# POWER.net
KiCad netlist of a schematic drawn in Altium Designer
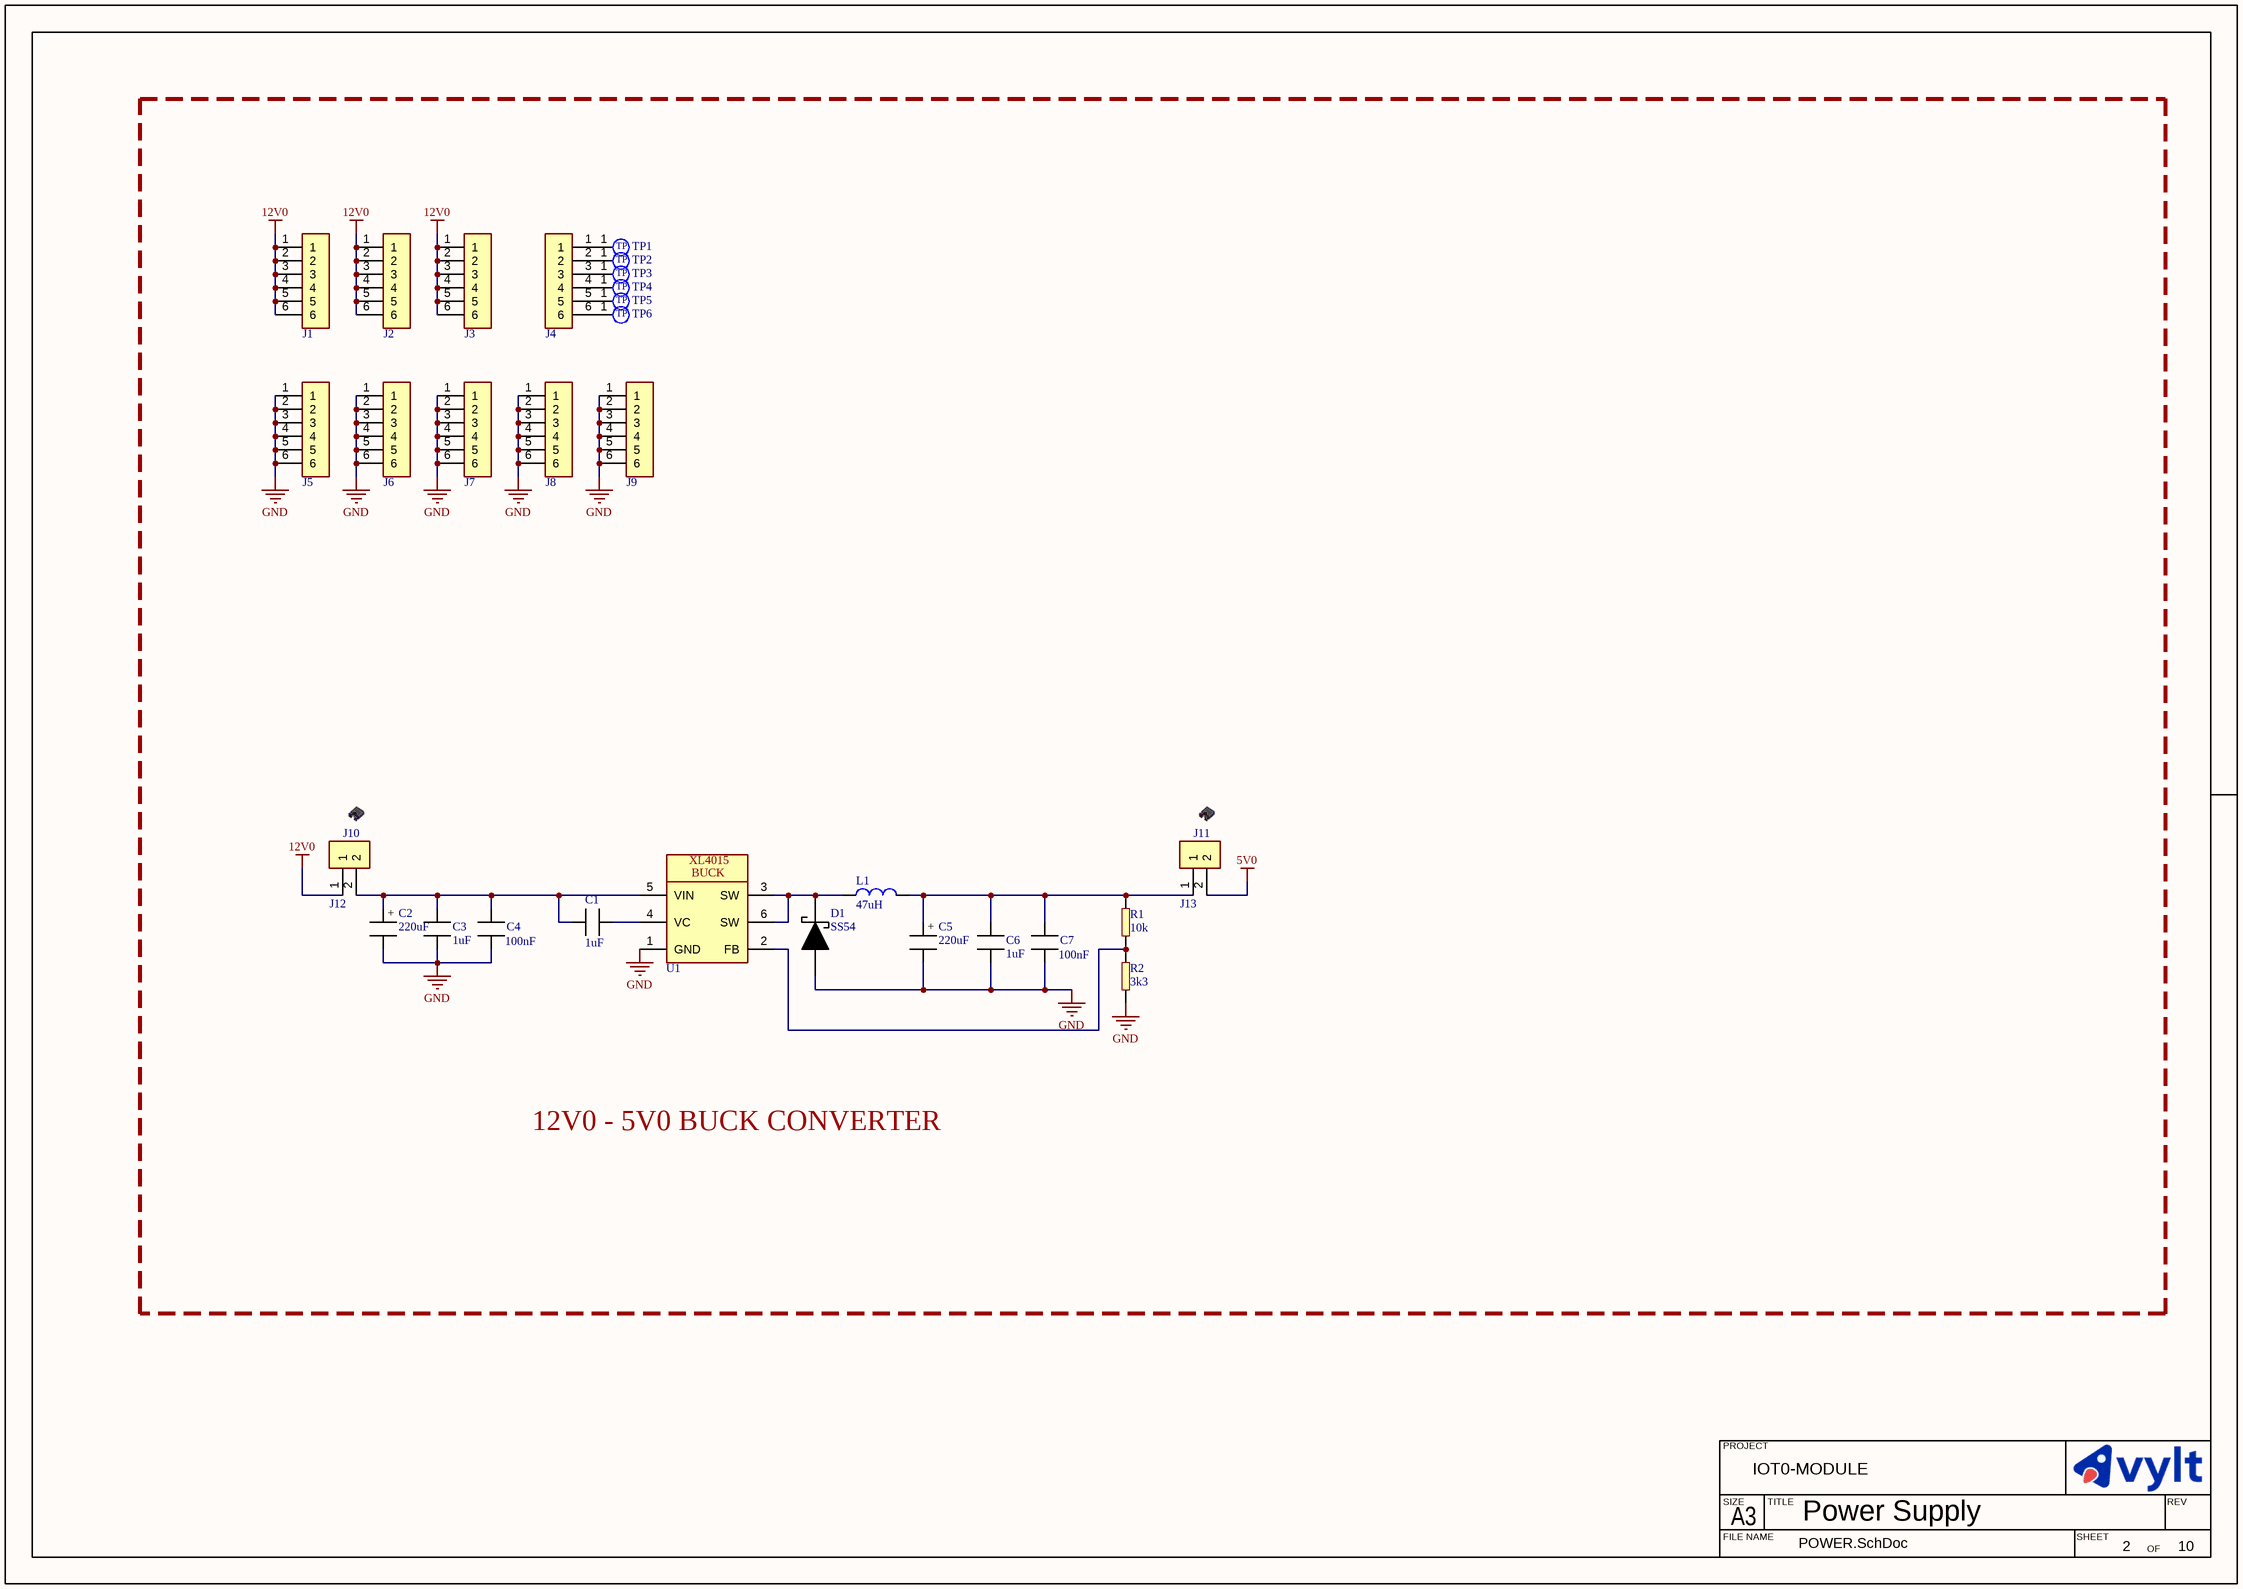
[diagram p0: POWER.SchDoc]

(export (version "E")
  (design (tool "Eeschema 10.0.6"))
  (components
    (comp (ref "C1")
      (value "1uF")
      (footprint "CAPC2012X13L")
      (description "Chip Capacitor, 2-Leads, Body 2.00x1.25mm, IPC High Density")
      (fields (field (name "Comment") "MLCC_0805"))
      (libsource (lib "Capacitor") (part "MLCC_0805"))
    )
    (comp (ref "C2")
      (value "220uF")
      (footprint "CAP_D10_H16_P5 - Flat")
      (description "Electrolytic Capacitor Through Hole D10 P5.0")
      (fields (field (name "Comment") "ERP_102-2"))
      (libsource (lib "ElectrolyticCapacitor") (part "CAP_D10_H16_P5"))
    )
    (comp (ref "C3")
      (value "1uF")
      (footprint "CAPC2012X13L")
      (description "Chip Capacitor, 2-Leads, Body 2.00x1.25mm, IPC High Density")
      (fields (field (name "Comment") "MLCC_0805"))
      (libsource (lib "Capacitor") (part "MLCC_0805"))
    )
    (comp (ref "C4")
      (value "100nF")
      (footprint "CAPC2012X13L")
      (description "Chip Capacitor, 2-Leads, Body 2.00x1.25mm, IPC High Density")
      (fields (field (name "Comment") "MLCC_0805"))
      (libsource (lib "Capacitor") (part "MLCC_0805"))
    )
    (comp (ref "C5")
      (value "220uF")
      (footprint "CAP_D10_H16_P5 - Flat")
      (description "Electrolytic Capacitor Through Hole D10 P5.0")
      (fields (field (name "Comment") "ERP_102-2"))
      (libsource (lib "ElectrolyticCapacitor") (part "CAP_D10_H16_P5"))
    )
    (comp (ref "C6")
      (value "1uF")
      (footprint "CAPC2012X13L")
      (description "Chip Capacitor, 2-Leads, Body 2.00x1.25mm, IPC High Density")
      (fields (field (name "Comment") "MLCC_0805"))
      (libsource (lib "Capacitor") (part "MLCC_0805"))
    )
    (comp (ref "C7")
      (value "100nF")
      (footprint "CAPC2012X13L")
      (description "Chip Capacitor, 2-Leads, Body 2.00x1.25mm, IPC High Density")
      (fields (field (name "Comment") "MLCC_0805"))
      (libsource (lib "Capacitor") (part "MLCC_0805"))
    )
    (comp (ref "D1")
      (value "SS54")
      (footprint "DIOM6959X26L")
      (fields (field (name "Comment") "ERP_104-3"))
      (libsource (lib "Schottky") (part "SS54"))
    )
    (comp (ref "J1")
      (value "6PX1R_M")
      (footprint "6PX1R_M_STK20")
      (description "6PX1R Male Header")
      (libsource (lib "PinHeader") (part "6PX1R_M"))
    )
    (comp (ref "J2")
      (value "6PX1R_M")
      (footprint "6PX1R_M_STK20")
      (description "6PX1R Male Header")
      (libsource (lib "PinHeader") (part "6PX1R_M"))
    )
    (comp (ref "J3")
      (value "6PX1R_M")
      (footprint "6PX1R_M_STK20")
      (description "6PX1R Male Header")
      (libsource (lib "PinHeader") (part "6PX1R_M"))
    )
    (comp (ref "J4")
      (value "6PX1R_M")
      (footprint "6PX1R_M_STK20")
      (description "6PX1R Male Header")
      (libsource (lib "") (part "6PX1R_M_1"))
    )
    (comp (ref "J5")
      (value "6PX1R_M")
      (footprint "6PX1R_M_STK20")
      (description "6PX1R Male Header")
      (libsource (lib "PinHeader") (part "6PX1R_M"))
    )
    (comp (ref "J6")
      (value "6PX1R_M")
      (footprint "6PX1R_M_STK20")
      (description "6PX1R Male Header")
      (libsource (lib "PinHeader") (part "6PX1R_M"))
    )
    (comp (ref "J7")
      (value "6PX1R_M")
      (footprint "6PX1R_M_STK20")
      (description "6PX1R Male Header")
      (libsource (lib "PinHeader") (part "6PX1R_M"))
    )
    (comp (ref "J8")
      (value "6PX1R_M")
      (footprint "6PX1R_M_STK20")
      (description "6PX1R Male Header")
      (libsource (lib "PinHeader") (part "6PX1R_M"))
    )
    (comp (ref "J9")
      (value "6PX1R_M")
      (footprint "6PX1R_M_STK20")
      (description "6PX1R Male Header")
      (libsource (lib "PinHeader") (part "6PX1R_M"))
    )
    (comp (ref "J10")
      (value "Jumper Cap")
      (description "2 Pin Jumper Cap P2.54")
      (libsource (lib "Jumper") (part "Jumper Cap"))
    )
    (comp (ref "J11")
      (value "Jumper Cap")
      (description "2 Pin Jumper Cap P2.54")
      (libsource (lib "Jumper") (part "Jumper Cap"))
    )
    (comp (ref "J12") (value "2PX1R") (footprint "2PX1R") (libsource (lib "PinHeader") (part "2PX1R")))
    (comp (ref "J13") (value "2PX1R") (footprint "2PX1R") (libsource (lib "PinHeader") (part "2PX1R")))
    (comp (ref "L1")
      (value "47uH")
      (footprint "IND_1212")
      (description "IND_1212")
      (fields (field (name "Comment") "ERP_103-3"))
      (libsource (lib "Inductor") (part "IND_1212"))
    )
    (comp (ref "R1")
      (value "10k")
      (footprint "RES_0603")
      (description "RES_0603")
      (fields (field (name "Comment") "ERP_101-1"))
      (libsource (lib "Resistor") (part "RES_0603"))
    )
    (comp (ref "R2")
      (value "3k3")
      (footprint "RES_0603")
      (description "RES_0603")
      (fields (field (name "Comment") "ERP_101-1"))
      (libsource (lib "Resistor") (part "RES_0603"))
    )
    (comp (ref "TP1") (value "TP_1MM") (footprint "TP_1MM") (libsource (lib "Jumper") (part "TP_1MM")))
    (comp (ref "TP2") (value "TP_1MM") (footprint "TP_1MM") (libsource (lib "Jumper") (part "TP_1MM")))
    (comp (ref "TP3") (value "TP_1MM") (footprint "TP_1MM") (libsource (lib "Jumper") (part "TP_1MM")))
    (comp (ref "TP4") (value "TP_1MM") (footprint "TP_1MM") (libsource (lib "Jumper") (part "TP_1MM")))
    (comp (ref "TP5") (value "TP_1MM") (footprint "TP_1MM") (libsource (lib "Jumper") (part "TP_1MM")))
    (comp (ref "TP6") (value "TP_1MM") (footprint "TP_1MM") (libsource (lib "Jumper") (part "TP_1MM")))
    (comp (ref "U1")
      (value "XL4015")
      (footprint "XL4015")
      (description "5A 180KHz 36V Buck DC to DC Converter")
      (libsource (lib "DCDC_Switcher") (part "XL4015"))
    )
  )
  (nets
    (net (code "1") (name "5V0") (class "Default")
      (node (ref "J13") (pin "2") (pinfunction "2_2") (pintype "passive"))
    )
    (net (code "2") (name "12V0") (class "Default")
      (node (ref "J1") (pin "1") (pinfunction "1_1") (pintype "passive"))
      (node (ref "J1") (pin "2") (pinfunction "2_2") (pintype "passive"))
      (node (ref "J1") (pin "3") (pinfunction "3_3") (pintype "passive"))
      (node (ref "J1") (pin "4") (pinfunction "4_4") (pintype "passive"))
      (node (ref "J1") (pin "5") (pinfunction "5_5") (pintype "passive"))
      (node (ref "J1") (pin "6") (pinfunction "6_6") (pintype "passive"))
      (node (ref "J12") (pin "1") (pinfunction "1_1") (pintype "passive"))
      (node (ref "J2") (pin "1") (pinfunction "1_1") (pintype "passive"))
      (node (ref "J2") (pin "2") (pinfunction "2_2") (pintype "passive"))
      (node (ref "J2") (pin "3") (pinfunction "3_3") (pintype "passive"))
      (node (ref "J2") (pin "4") (pinfunction "4_4") (pintype "passive"))
      (node (ref "J2") (pin "5") (pinfunction "5_5") (pintype "passive"))
      (node (ref "J2") (pin "6") (pinfunction "6_6") (pintype "passive"))
      (node (ref "J3") (pin "1") (pinfunction "1_1") (pintype "passive"))
      (node (ref "J3") (pin "2") (pinfunction "2_2") (pintype "passive"))
      (node (ref "J3") (pin "3") (pinfunction "3_3") (pintype "passive"))
      (node (ref "J3") (pin "4") (pinfunction "4_4") (pintype "passive"))
      (node (ref "J3") (pin "5") (pinfunction "5_5") (pintype "passive"))
      (node (ref "J3") (pin "6") (pinfunction "6_6") (pintype "passive"))
    )
    (net (code "3") (name "GND") (class "Default")
      (node (ref "C2") (pin "2") (pinfunction "2_2") (pintype "passive"))
      (node (ref "C3") (pin "1") (pinfunction "1_1") (pintype "passive"))
      (node (ref "C4") (pin "2") (pinfunction "2_2") (pintype "passive"))
      (node (ref "C5") (pin "2") (pinfunction "2_2") (pintype "passive"))
      (node (ref "C6") (pin "1") (pinfunction "1_1") (pintype "passive"))
      (node (ref "C7") (pin "2") (pinfunction "2_2") (pintype "passive"))
      (node (ref "D1") (pin "2") (pinfunction "A_2") (pintype "passive"))
      (node (ref "J5") (pin "1") (pinfunction "1_1") (pintype "passive"))
      (node (ref "J5") (pin "2") (pinfunction "2_2") (pintype "passive"))
      (node (ref "J5") (pin "3") (pinfunction "3_3") (pintype "passive"))
      (node (ref "J5") (pin "4") (pinfunction "4_4") (pintype "passive"))
      (node (ref "J5") (pin "5") (pinfunction "5_5") (pintype "passive"))
      (node (ref "J5") (pin "6") (pinfunction "6_6") (pintype "passive"))
      (node (ref "J6") (pin "1") (pinfunction "1_1") (pintype "passive"))
      (node (ref "J6") (pin "2") (pinfunction "2_2") (pintype "passive"))
      (node (ref "J6") (pin "3") (pinfunction "3_3") (pintype "passive"))
      (node (ref "J6") (pin "4") (pinfunction "4_4") (pintype "passive"))
      (node (ref "J6") (pin "5") (pinfunction "5_5") (pintype "passive"))
      (node (ref "J6") (pin "6") (pinfunction "6_6") (pintype "passive"))
      (node (ref "J7") (pin "1") (pinfunction "1_1") (pintype "passive"))
      (node (ref "J7") (pin "2") (pinfunction "2_2") (pintype "passive"))
      (node (ref "J7") (pin "3") (pinfunction "3_3") (pintype "passive"))
      (node (ref "J7") (pin "4") (pinfunction "4_4") (pintype "passive"))
      (node (ref "J7") (pin "5") (pinfunction "5_5") (pintype "passive"))
      (node (ref "J7") (pin "6") (pinfunction "6_6") (pintype "passive"))
      (node (ref "J8") (pin "1") (pinfunction "1_1") (pintype "passive"))
      (node (ref "J8") (pin "2") (pinfunction "2_2") (pintype "passive"))
      (node (ref "J8") (pin "3") (pinfunction "3_3") (pintype "passive"))
      (node (ref "J8") (pin "4") (pinfunction "4_4") (pintype "passive"))
      (node (ref "J8") (pin "5") (pinfunction "5_5") (pintype "passive"))
      (node (ref "J8") (pin "6") (pinfunction "6_6") (pintype "passive"))
      (node (ref "J9") (pin "1") (pinfunction "1_1") (pintype "passive"))
      (node (ref "J9") (pin "2") (pinfunction "2_2") (pintype "passive"))
      (node (ref "J9") (pin "3") (pinfunction "3_3") (pintype "passive"))
      (node (ref "J9") (pin "4") (pinfunction "4_4") (pintype "passive"))
      (node (ref "J9") (pin "5") (pinfunction "5_5") (pintype "passive"))
      (node (ref "J9") (pin "6") (pinfunction "6_6") (pintype "passive"))
      (node (ref "R2") (pin "2") (pinfunction "2_2") (pintype "passive"))
      (node (ref "U1") (pin "1") (pinfunction "GND_1") (pintype "passive"))
    )
    (net (code "4") (name "Net-(C5-Pad1)") (class "Default")
      (node (ref "C5") (pin "1") (pinfunction "1_1") (pintype "passive"))
      (node (ref "C6") (pin "2") (pinfunction "2_2") (pintype "passive"))
      (node (ref "C7") (pin "1") (pinfunction "1_1") (pintype "passive"))
      (node (ref "J13") (pin "1") (pinfunction "1_1") (pintype "passive"))
      (node (ref "L1") (pin "2") (pinfunction "2_2") (pintype "passive"))
      (node (ref "R1") (pin "1") (pinfunction "1_1") (pintype "passive"))
    )
    (net (code "5") (name "Net-(D1-C)") (class "Default")
      (node (ref "D1") (pin "1") (pinfunction "C_1") (pintype "passive"))
      (node (ref "L1") (pin "1") (pinfunction "1_1") (pintype "passive"))
      (node (ref "U1") (pin "3") (pinfunction "SW_3") (pintype "passive"))
      (node (ref "U1") (pin "6") (pinfunction "SW_6") (pintype "passive"))
    )
    (net (code "6") (name "Net-(J4-Pad1)") (class "Default")
      (node (ref "J4") (pin "1") (pinfunction "1_1") (pintype "passive"))
      (node (ref "TP1") (pin "1") (pinfunction "1_1") (pintype "passive"))
    )
    (net (code "7") (name "Net-(J4-Pad2)") (class "Default")
      (node (ref "J4") (pin "2") (pinfunction "2_2") (pintype "passive"))
      (node (ref "TP2") (pin "1") (pinfunction "1_1") (pintype "passive"))
    )
    (net (code "8") (name "Net-(J4-Pad3)") (class "Default")
      (node (ref "J4") (pin "3") (pinfunction "3_3") (pintype "passive"))
      (node (ref "TP3") (pin "1") (pinfunction "1_1") (pintype "passive"))
    )
    (net (code "9") (name "Net-(J4-Pad4)") (class "Default")
      (node (ref "J4") (pin "4") (pinfunction "4_4") (pintype "passive"))
      (node (ref "TP4") (pin "1") (pinfunction "1_1") (pintype "passive"))
    )
    (net (code "10") (name "Net-(J4-Pad5)") (class "Default")
      (node (ref "J4") (pin "5") (pinfunction "5_5") (pintype "passive"))
      (node (ref "TP5") (pin "1") (pinfunction "1_1") (pintype "passive"))
    )
    (net (code "11") (name "Net-(J4-Pad6)") (class "Default")
      (node (ref "J4") (pin "6") (pinfunction "6_6") (pintype "passive"))
      (node (ref "TP6") (pin "1") (pinfunction "1_1") (pintype "passive"))
    )
    (net (code "12") (name "Net-(U1-FB)") (class "Default")
      (node (ref "R1") (pin "2") (pinfunction "2_2") (pintype "passive"))
      (node (ref "R2") (pin "1") (pinfunction "1_1") (pintype "passive"))
      (node (ref "U1") (pin "2") (pinfunction "FB_2") (pintype "passive"))
    )
    (net (code "13") (name "Net-(U1-VC)") (class "Default")
      (node (ref "C1") (pin "2") (pinfunction "2_2") (pintype "passive"))
      (node (ref "U1") (pin "4") (pinfunction "VC_4") (pintype "passive"))
    )
    (net (code "14") (name "Net-(U1-VIN)") (class "Default")
      (node (ref "C1") (pin "1") (pinfunction "1_1") (pintype "passive"))
      (node (ref "C2") (pin "1") (pinfunction "1_1") (pintype "passive"))
      (node (ref "C3") (pin "2") (pinfunction "2_2") (pintype "passive"))
      (node (ref "C4") (pin "1") (pinfunction "1_1") (pintype "passive"))
      (node (ref "J12") (pin "2") (pinfunction "2_2") (pintype "passive"))
      (node (ref "U1") (pin "5") (pinfunction "VIN_5") (pintype "passive"))
    )
  )
)
